# 01_-_CPU.net
KiCad netlist of a schematic drawn in Altium Designer
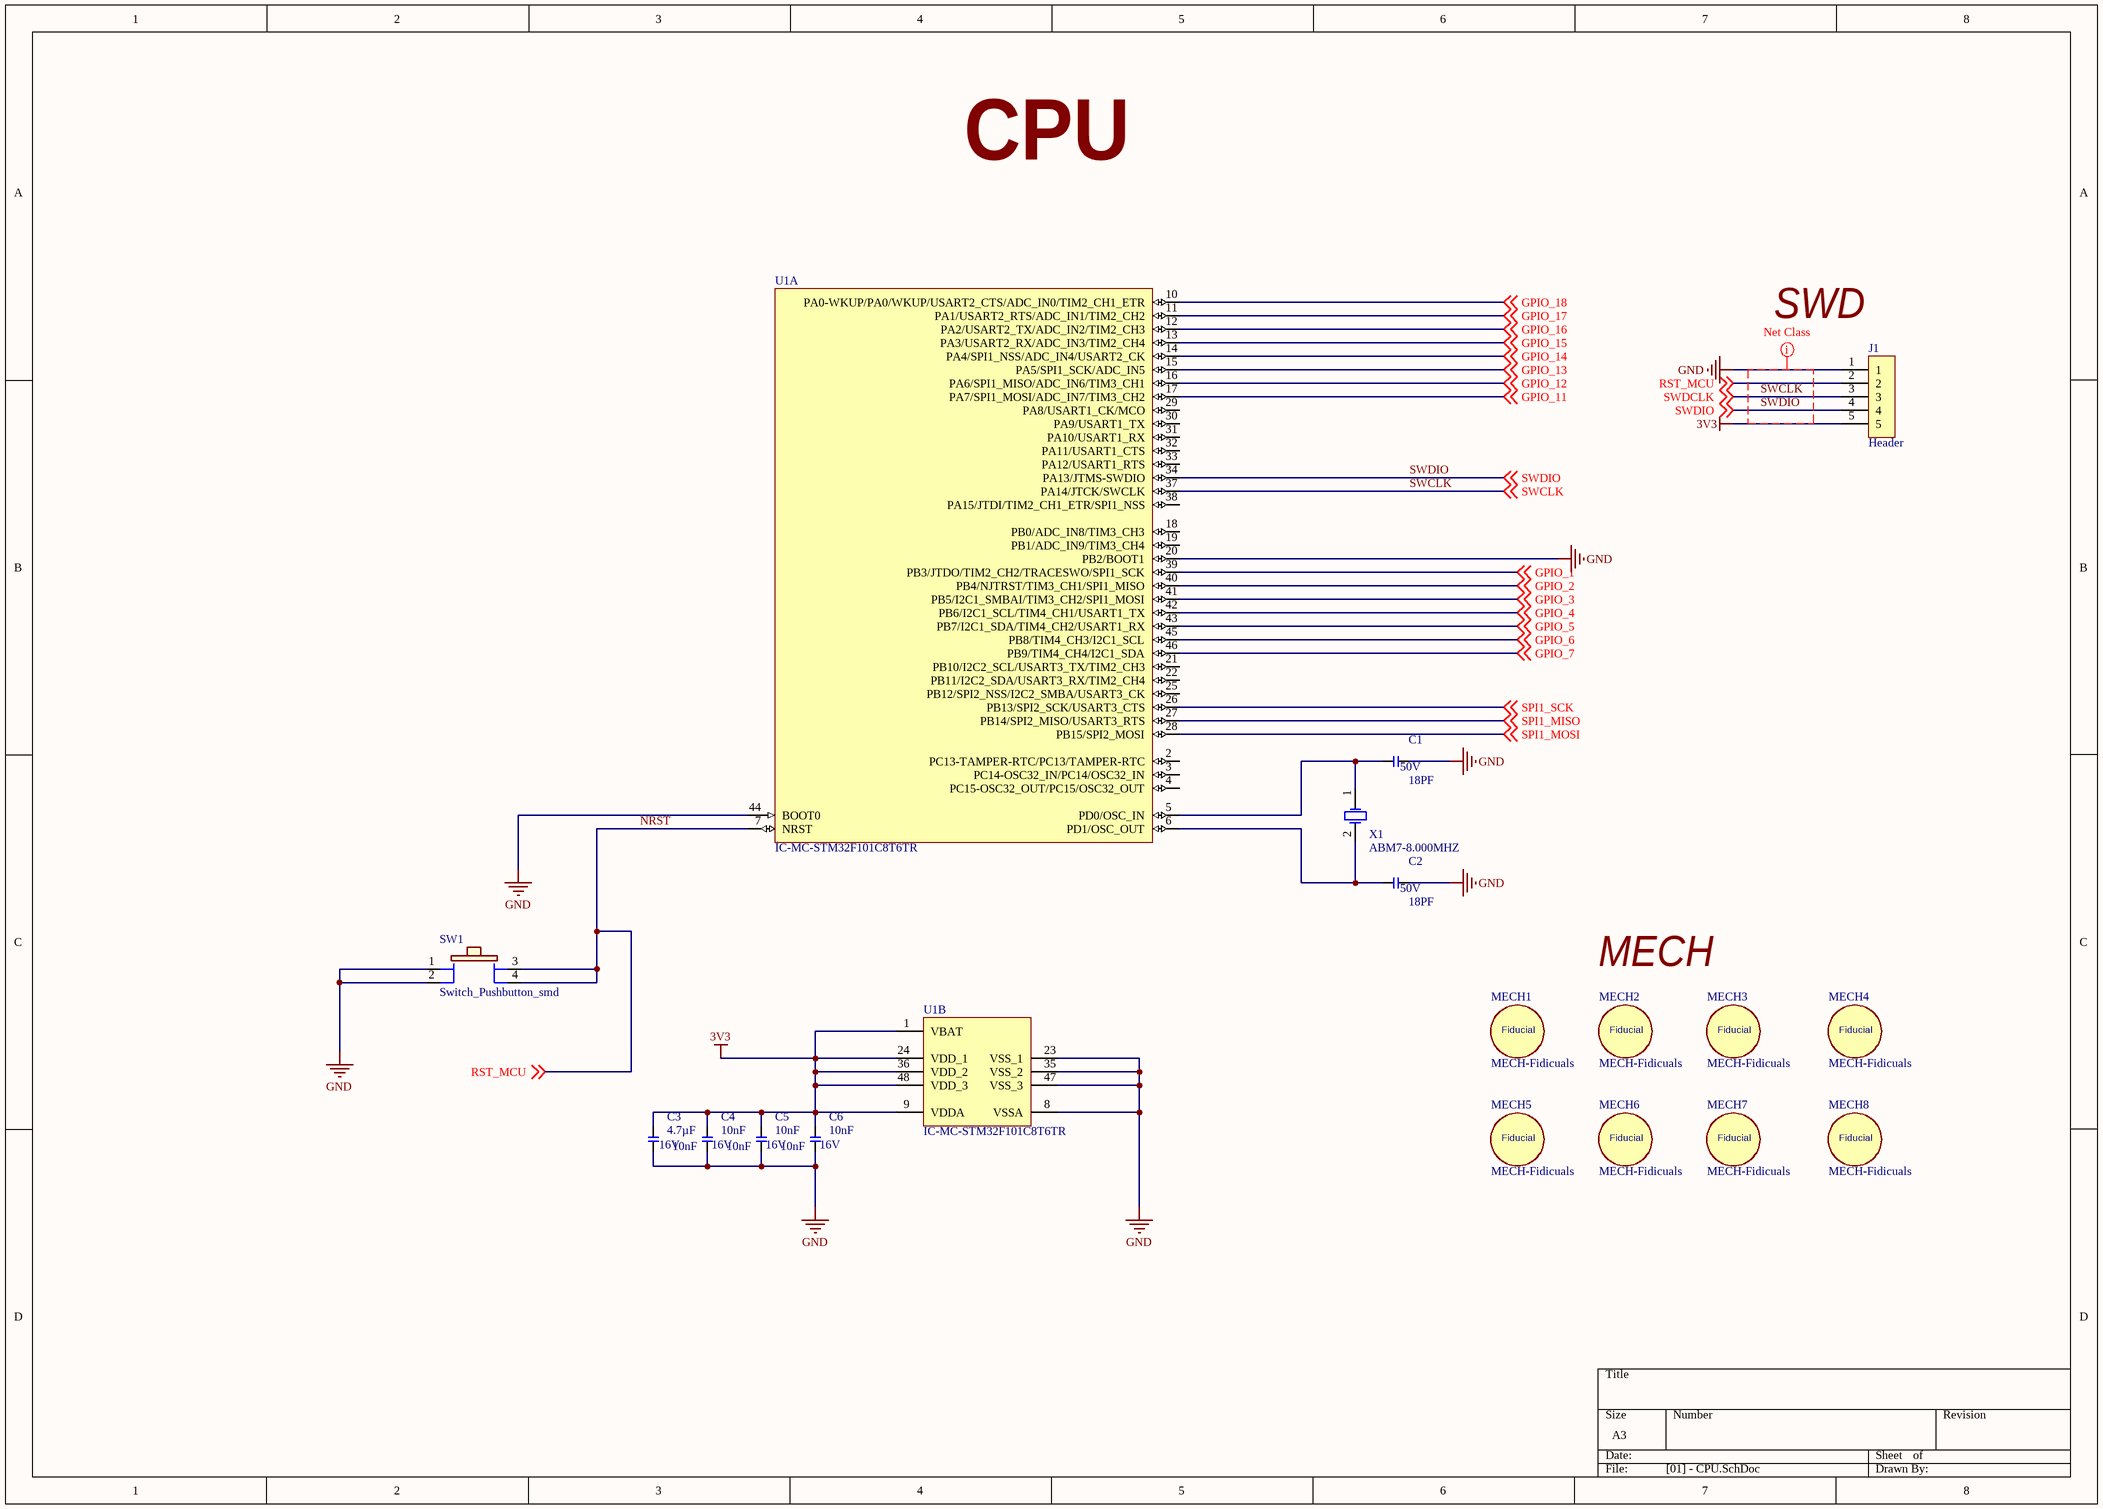
[diagram p0: [01] - CPU.SchDoc]

(export (version "E")
  (design (tool "Eeschema 10.0.6"))
  (components
    (comp (ref "C1")
      (value "18PF")
      (footprint "C0805")
      (description "MULTICOMP - MC0805N180J500CT - CAP, MLCC, C0G/NP0, 18PF, 50V,0805, REEL")
      (fields
        (field (name "MANUFACTURER") "Multicomp")
        (field (name "MANUFACTURER PART NUMBER") "MC0805N180J500CT")
        (field (name "VOLTAGE_RATING_DC") "50V")
      )
      (libsource (lib "CPU_STM_080816") (part "C-18PF,50V,0805"))
    )
    (comp (ref "C2")
      (value "18PF")
      (footprint "C0805")
      (description "MULTICOMP - MC0805N180J500CT - CAP, MLCC, C0G/NP0, 18PF, 50V,0805, REEL")
      (fields
        (field (name "MANUFACTURER") "Multicomp")
        (field (name "MANUFACTURER PART NUMBER") "MC0805N180J500CT")
        (field (name "VOLTAGE_RATING_DC") "50V")
      )
      (libsource (lib "CPU_STM_080816") (part "C-18PF,50V,0805"))
    )
    (comp (ref "C3")
      (value "4.7µF")
      (footprint "C0805")
      (description "AVX - 0805YC475KAT2A - CAP, MLCC, X7R, 4.7UF, 16V, 0805")
      (fields
        (field (name "MANUFACTURER") "AVX Corporation")
        (field (name "MANUFACTURER PART NUMBER") "0805YC475KAT2A")
        (field (name "VOLTAGE - RATED") "16V")
      )
      (libsource (lib "CPU_STM_080816") (part "C-4.7UF,16V,0805"))
    )
    (comp (ref "C4")
      (value "10nF")
      (footprint "C0805")
      (description "CAP CER 10000PF 16V NP0 0805")
      (fields
        (field (name "MANUFACTURER") "AVX Corporation")
        (field (name "MANUFACTURER PART NUMBER") "0805YA103JAT2A")
        (field (name "CAPACITANCE") "10nF")
        (field (name "VOLTAGE - RATED") "16V")
      )
      (libsource (lib "CPU_STM_080816") (part "C-10NF,16V,0805"))
    )
    (comp (ref "C5")
      (value "10nF")
      (footprint "C0805")
      (description "CAP CER 10000PF 16V NP0 0805")
      (fields
        (field (name "MANUFACTURER") "AVX Corporation")
        (field (name "MANUFACTURER PART NUMBER") "0805YA103JAT2A")
        (field (name "CAPACITANCE") "10nF")
        (field (name "VOLTAGE - RATED") "16V")
      )
      (libsource (lib "CPU_STM_080816") (part "C-10NF,16V,0805"))
    )
    (comp (ref "C6")
      (value "10nF")
      (footprint "C0805")
      (description "CAP CER 10000PF 16V NP0 0805")
      (fields
        (field (name "MANUFACTURER") "AVX Corporation")
        (field (name "MANUFACTURER PART NUMBER") "0805YA103JAT2A")
        (field (name "CAPACITANCE") "10nF")
        (field (name "VOLTAGE - RATED") "16V")
      )
      (libsource (lib "CPU_STM_080816") (part "C-10NF,16V,0805"))
    )
    (comp (ref "J1")
      (value "Header")
      (footprint "Header 1x5 2.54mm")
      (description "Header 1X5 2.54")
      (libsource (lib "CPU_STM_080816") (part "CON-Header 1X5 2.54MM"))
    )
    (comp (ref "MECH1")
      (value "MECH-Fidicuals")
      (footprint "T-Fidicuals")
      (description "Fidicuals")
      (libsource (lib "CPU_STM_080816") (part "MECH-Fidicuals"))
    )
    (comp (ref "MECH2")
      (value "MECH-Fidicuals")
      (footprint "T-Fidicuals")
      (description "Fidicuals")
      (libsource (lib "CPU_STM_080816") (part "MECH-Fidicuals"))
    )
    (comp (ref "MECH3")
      (value "MECH-Fidicuals")
      (footprint "T-Fidicuals")
      (description "Fidicuals")
      (libsource (lib "CPU_STM_080816") (part "MECH-Fidicuals"))
    )
    (comp (ref "MECH4")
      (value "MECH-Fidicuals")
      (footprint "T-Fidicuals")
      (description "Fidicuals")
      (libsource (lib "CPU_STM_080816") (part "MECH-Fidicuals"))
    )
    (comp (ref "MECH5")
      (value "MECH-Fidicuals")
      (footprint "T-Fidicuals")
      (description "Fidicuals")
      (libsource (lib "CPU_STM_080816") (part "MECH-Fidicuals"))
    )
    (comp (ref "MECH6")
      (value "MECH-Fidicuals")
      (footprint "T-Fidicuals")
      (description "Fidicuals")
      (libsource (lib "CPU_STM_080816") (part "MECH-Fidicuals"))
    )
    (comp (ref "MECH7")
      (value "MECH-Fidicuals")
      (footprint "T-Fidicuals")
      (description "Fidicuals")
      (libsource (lib "CPU_STM_080816") (part "MECH-Fidicuals"))
    )
    (comp (ref "MECH8")
      (value "MECH-Fidicuals")
      (footprint "T-Fidicuals")
      (description "Fidicuals")
      (libsource (lib "CPU_STM_080816") (part "MECH-Fidicuals"))
    )
    (comp (ref "SW1")
      (value "Switch_Pushbutton_smd")
      (footprint "SW_B3SL-1022P")
      (description "Switch Push Button tactile")
      (fields (field (name "TIINTPARTNUMBER") "2W0018") (field (name "MFR") "Omron"))
      (libsource (lib "CPU_STM_080816") (part "Switch_Pushbutton_smd"))
    )
    (comp (ref "U1")
      (value "IC-MC-STM32F101C8T6TR")
      (footprint "STM-LQFP48_M")
      (description "IC MCU 32BIT 64KB FLASH 48LQFP")
      (fields
        (field (name "MANUFACTURER") "STMicroelectronics")
        (field (name "MANUFACTURER PART NUMBER") "STM32F101C8T6TR")
      )
      (libsource (lib "CPU_STM_080816") (part "IC-MC-STM32F101C8T6TR"))
    )
    (comp (ref "X1")
      (value "ABM7-8.000MHZ")
      (footprint "sm_osc_mixed")
      (description "CRYSTAL 8.0000MHZ 18PF SMD")
      (fields
        (field (name "MANUFACTURER") "Abracon LLC")
        (field (name "MANUFACTURER PART NUMBER") "ABM7-8.000MHZ-D2Y-T")
      )
      (libsource (lib "CPU_STM_080816") (part "OSC-ABM7-8.000MHZ-D2Y-T"))
    )
  )
  (nets
    (net (code "1") (name "3V3") (class "Default")
      (node (ref "C3") (pin "2") (pinfunction "2_2") (pintype "passive"))
      (node (ref "C4") (pin "2") (pinfunction "2_2") (pintype "passive"))
      (node (ref "C5") (pin "2") (pinfunction "2_2") (pintype "passive"))
      (node (ref "C6") (pin "2") (pinfunction "2_2") (pintype "passive"))
      (node (ref "J1") (pin "5") (pinfunction "5_5") (pintype "passive"))
      (node (ref "U1") (pin "1") (pinfunction "VBAT_1") (pintype "power_in"))
      (node (ref "U1") (pin "24") (pinfunction "VDD_1_24") (pintype "power_in"))
      (node (ref "U1") (pin "36") (pinfunction "VDD_2_36") (pintype "power_in"))
      (node (ref "U1") (pin "48") (pinfunction "VDD_3_48") (pintype "power_in"))
      (node (ref "U1") (pin "9") (pinfunction "VDDA_9") (pintype "power_in"))
    )
    (net (code "2") (name "GND") (class "Default")
      (node (ref "C1") (pin "2") (pinfunction "2_2") (pintype "passive"))
      (node (ref "C2") (pin "2") (pinfunction "2_2") (pintype "passive"))
      (node (ref "C3") (pin "1") (pinfunction "1_1") (pintype "passive"))
      (node (ref "C4") (pin "1") (pinfunction "1_1") (pintype "passive"))
      (node (ref "C5") (pin "1") (pinfunction "1_1") (pintype "passive"))
      (node (ref "C6") (pin "1") (pinfunction "1_1") (pintype "passive"))
      (node (ref "J1") (pin "1") (pinfunction "1_1") (pintype "passive"))
      (node (ref "SW1") (pin "1") (pinfunction "1_1") (pintype "passive"))
      (node (ref "SW1") (pin "2") (pinfunction "2_2") (pintype "passive"))
      (node (ref "U1") (pin "20") (pinfunction "PB2/BOOT1_20") (pintype "bidirectional"))
      (node (ref "U1") (pin "23") (pinfunction "VSS_1_23") (pintype "power_in"))
      (node (ref "U1") (pin "35") (pinfunction "VSS_2_35") (pintype "power_in"))
      (node (ref "U1") (pin "44") (pinfunction "BOOT0_44") (pintype "input"))
      (node (ref "U1") (pin "47") (pinfunction "VSS_3_47") (pintype "power_in"))
      (node (ref "U1") (pin "8") (pinfunction "VSSA_8") (pintype "power_in"))
    )
    (net (code "3") (name "GPIO_1") (class "Default")
      (node (ref "U1") (pin "39") (pinfunction "PB3/JTDO/TIM2_CH2/TRACESWO/SPI1_SCK_39") (pintype "bidirectional"))
    )
    (net (code "4") (name "GPIO_2") (class "Default")
      (node (ref "U1") (pin "40") (pinfunction "PB4/NJTRST/TIM3_CH1/SPI1_MISO_40") (pintype "bidirectional"))
    )
    (net (code "5") (name "GPIO_3") (class "Default")
      (node (ref "U1") (pin "41") (pinfunction "PB5/I2C1_SMBAI/TIM3_CH2/SPI1_MOSI_41") (pintype "bidirectional"))
    )
    (net (code "6") (name "GPIO_4") (class "Default")
      (node (ref "U1") (pin "42") (pinfunction "PB6/I2C1_SCL/TIM4_CH1/USART1_TX_42") (pintype "bidirectional"))
    )
    (net (code "7") (name "GPIO_5") (class "Default")
      (node (ref "U1") (pin "43") (pinfunction "PB7/I2C1_SDA/TIM4_CH2/USART1_RX_43") (pintype "bidirectional"))
    )
    (net (code "8") (name "GPIO_6") (class "Default")
      (node (ref "U1") (pin "45") (pinfunction "PB8/TIM4_CH3/I2C1_SCL_45") (pintype "bidirectional"))
    )
    (net (code "9") (name "GPIO_7") (class "Default")
      (node (ref "U1") (pin "46") (pinfunction "PB9/TIM4_CH4/I2C1_SDA_46") (pintype "bidirectional"))
    )
    (net (code "10") (name "GPIO_11") (class "Default")
      (node (ref "U1") (pin "17") (pinfunction "PA7/SPI1_MOSI/ADC_IN7/TIM3_CH2_17") (pintype "bidirectional"))
    )
    (net (code "11") (name "GPIO_12") (class "Default")
      (node (ref "U1") (pin "16") (pinfunction "PA6/SPI1_MISO/ADC_IN6/TIM3_CH1_16") (pintype "bidirectional"))
    )
    (net (code "12") (name "GPIO_13") (class "Default")
      (node (ref "U1") (pin "15") (pinfunction "PA5/SPI1_SCK/ADC_IN5_15") (pintype "bidirectional"))
    )
    (net (code "13") (name "GPIO_14") (class "Default")
      (node (ref "U1") (pin "14") (pinfunction "PA4/SPI1_NSS/ADC_IN4/USART2_CK_14") (pintype "bidirectional"))
    )
    (net (code "14") (name "GPIO_15") (class "Default")
      (node (ref "U1") (pin "13") (pinfunction "PA3/USART2_RX/ADC_IN3/TIM2_CH4_13") (pintype "bidirectional"))
    )
    (net (code "15") (name "GPIO_16") (class "Default")
      (node (ref "U1") (pin "12") (pinfunction "PA2/USART2_TX/ADC_IN2/TIM2_CH3_12") (pintype "bidirectional"))
    )
    (net (code "16") (name "GPIO_17") (class "Default")
      (node (ref "U1") (pin "11") (pinfunction "PA1/USART2_RTS/ADC_IN1/TIM2_CH2_11") (pintype "bidirectional"))
    )
    (net (code "17") (name "GPIO_18") (class "Default")
      (node (ref "U1") (pin "10") (pinfunction "PA0-WKUP/PA0/WKUP/USART2_CTS/ADC_IN0/TIM2_CH1_ETR_10") (pintype "bidirectional"))
    )
    (net (code "18") (name "Net-(U1A-PD0{slash}OSC_IN)") (class "Default")
      (node (ref "C1") (pin "1") (pinfunction "1_1") (pintype "passive"))
      (node (ref "U1") (pin "5") (pinfunction "PD0/OSC_IN_5") (pintype "bidirectional"))
      (node (ref "X1") (pin "1") (pinfunction "OSC1_1") (pintype "passive"))
    )
    (net (code "19") (name "Net-(U1A-PD1{slash}OSC_OUT)") (class "Default")
      (node (ref "C2") (pin "1") (pinfunction "1_1") (pintype "passive"))
      (node (ref "U1") (pin "6") (pinfunction "PD1/OSC_OUT_6") (pintype "bidirectional"))
      (node (ref "X1") (pin "2") (pinfunction "OSC2_2") (pintype "passive"))
    )
    (net (code "20") (name "RST_MCU") (class "Default")
      (node (ref "J1") (pin "2") (pinfunction "2_2") (pintype "passive"))
      (node (ref "SW1") (pin "3") (pinfunction "3_3") (pintype "passive"))
      (node (ref "SW1") (pin "4") (pinfunction "4_4") (pintype "passive"))
      (node (ref "U1") (pin "7") (pinfunction "NRST_7") (pintype "bidirectional"))
    )
    (net (code "21") (name "SPI1_MISO") (class "Default")
      (node (ref "U1") (pin "27") (pinfunction "PB14/SPI2_MISO/USART3_RTS_27") (pintype "bidirectional"))
    )
    (net (code "22") (name "SPI1_MOSI") (class "Default")
      (node (ref "U1") (pin "28") (pinfunction "PB15/SPI2_MOSI_28") (pintype "bidirectional"))
    )
    (net (code "23") (name "SPI1_SCK") (class "Default")
      (node (ref "U1") (pin "26") (pinfunction "PB13/SPI2_SCK/USART3_CTS_26") (pintype "bidirectional"))
    )
    (net (code "24") (name "SWCLK") (class "Default")
      (node (ref "J1") (pin "3") (pinfunction "3_3") (pintype "passive"))
      (node (ref "U1") (pin "37") (pinfunction "PA14/JTCK/SWCLK_37") (pintype "bidirectional"))
    )
    (net (code "25") (name "SWDIO") (class "Default")
      (node (ref "J1") (pin "4") (pinfunction "4_4") (pintype "passive"))
      (node (ref "U1") (pin "34") (pinfunction "PA13/JTMS-SWDIO_34") (pintype "bidirectional"))
    )
    (net (code "26") (name "unconnected-(U1A-PA8{slash}USART1_CK{slash}MCO-Pad29)") (class "Default")
      (node (ref "U1") (pin "29") (pinfunction "PA8/USART1_CK/MCO_29") (pintype "bidirectional"))
    )
    (net (code "27") (name "unconnected-(U1A-PA9{slash}USART1_TX-Pad30)") (class "Default")
      (node (ref "U1") (pin "30") (pinfunction "PA9/USART1_TX_30") (pintype "bidirectional"))
    )
    (net (code "28") (name "unconnected-(U1A-PA10{slash}USART1_RX-Pad31)") (class "Default")
      (node (ref "U1") (pin "31") (pinfunction "PA10/USART1_RX_31") (pintype "bidirectional"))
    )
    (net (code "29") (name "unconnected-(U1A-PA11{slash}USART1_CTS-Pad32)") (class "Default")
      (node (ref "U1") (pin "32") (pinfunction "PA11/USART1_CTS_32") (pintype "bidirectional"))
    )
    (net (code "30") (name "unconnected-(U1A-PA12{slash}USART1_RTS-Pad33)") (class "Default")
      (node (ref "U1") (pin "33") (pinfunction "PA12/USART1_RTS_33") (pintype "bidirectional"))
    )
    (net (code "31") (name "unconnected-(U1A-PA15{slash}JTDI{slash}TIM2_CH1_ETR{slash}SPI1_NSS-Pad38)") (class "Default")
      (node (ref "U1") (pin "38") (pinfunction "PA15/JTDI/TIM2_CH1_ETR/SPI1_NSS_38") (pintype "bidirectional"))
    )
    (net (code "32") (name "unconnected-(U1A-PB0{slash}ADC_IN8{slash}TIM3_CH3-Pad18)") (class "Default")
      (node (ref "U1") (pin "18") (pinfunction "PB0/ADC_IN8/TIM3_CH3_18") (pintype "bidirectional"))
    )
    (net (code "33") (name "unconnected-(U1A-PB1{slash}ADC_IN9{slash}TIM3_CH4-Pad19)") (class "Default")
      (node (ref "U1") (pin "19") (pinfunction "PB1/ADC_IN9/TIM3_CH4_19") (pintype "bidirectional"))
    )
    (net (code "34") (name "unconnected-(U1A-PB10{slash}I2C2_SCL{slash}USART3_TX{slash}TIM2_CH3-Pad21)") (class "Default")
      (node (ref "U1") (pin "21") (pinfunction "PB10/I2C2_SCL/USART3_TX/TIM2_CH3_21") (pintype "bidirectional"))
    )
    (net (code "35") (name "unconnected-(U1A-PB11{slash}I2C2_SDA{slash}USART3_RX{slash}TIM2_CH4-Pad22)") (class "Default")
      (node (ref "U1") (pin "22") (pinfunction "PB11/I2C2_SDA/USART3_RX/TIM2_CH4_22") (pintype "bidirectional"))
    )
    (net (code "36") (name "unconnected-(U1A-PB12{slash}SPI2_NSS{slash}I2C2_SMBA{slash}USART3_CK-Pad25)") (class "Default")
      (node (ref "U1") (pin "25") (pinfunction "PB12/SPI2_NSS/I2C2_SMBA/USART3_CK_25") (pintype "bidirectional"))
    )
    (net (code "37") (name "unconnected-(U1A-PC13-TAMPER-RTC{slash}PC13{slash}TAMPER-RTC-Pad2)") (class "Default")
      (node (ref "U1") (pin "2") (pinfunction "PC13-TAMPER-RTC/PC13/TAMPER-RTC_2") (pintype "bidirectional"))
    )
    (net (code "38") (name "unconnected-(U1A-PC14-OSC32_IN{slash}PC14{slash}OSC32_IN-Pad3)") (class "Default")
      (node (ref "U1") (pin "3") (pinfunction "PC14-OSC32_IN/PC14/OSC32_IN_3") (pintype "bidirectional"))
    )
    (net (code "39") (name "unconnected-(U1A-PC15-OSC32_OUT{slash}PC15{slash}OSC32_OUT-Pad4)") (class "Default")
      (node (ref "U1") (pin "4") (pinfunction "PC15-OSC32_OUT/PC15/OSC32_OUT_4") (pintype "bidirectional"))
    )
  )
)
